# Payload_exterior_v1_0.net
KiCad netlist of a schematic drawn in EAGLE
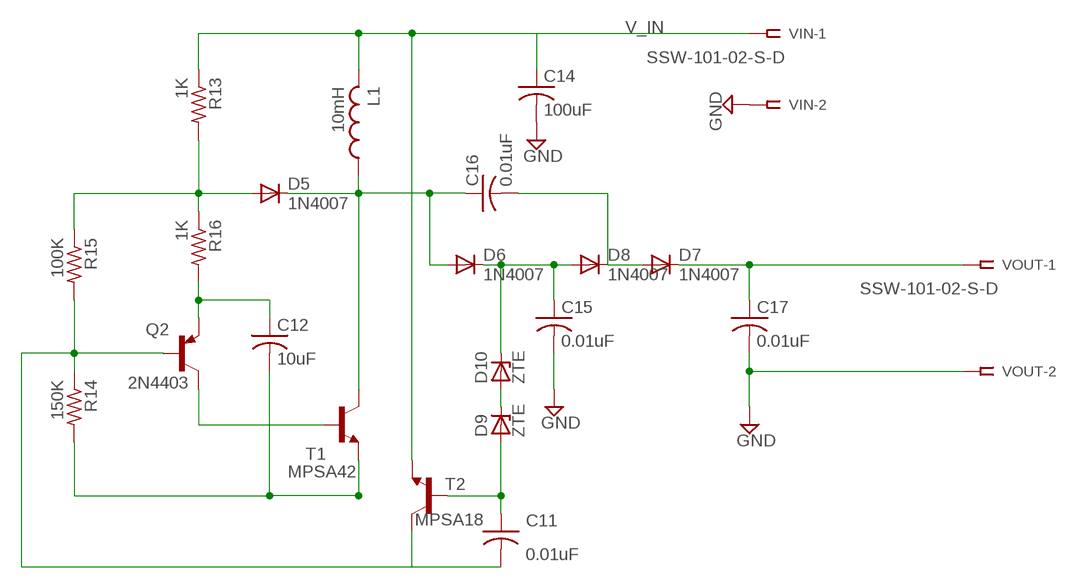
[diagram p0: schematic, sheet 1]

(export (version "E")
  (design (tool "Eeschema 10.0.6"))
  (components
    (comp (ref "C11")
      (value "0.01uF")
      (footprint "eagle-import:C050-035X075")
      (libsource (lib "eagle-import") (part "C-US050-035X075"))
    )
    (comp (ref "C12")
      (value "10uF")
      (footprint "eagle-import:C050-035X075")
      (libsource (lib "eagle-import") (part "C-US050-035X075"))
    )
    (comp (ref "C14")
      (value "100uF")
      (footprint "eagle-import:C050-035X075")
      (libsource (lib "eagle-import") (part "C-US050-035X075"))
    )
    (comp (ref "C15")
      (value "0.01uF")
      (footprint "eagle-import:C050-035X075")
      (libsource (lib "eagle-import") (part "C-US050-035X075"))
    )
    (comp (ref "C16")
      (value "0.01uF")
      (footprint "eagle-import:C050-035X075")
      (libsource (lib "eagle-import") (part "C-US050-035X075"))
    )
    (comp (ref "C17")
      (value "0.01uF")
      (footprint "eagle-import:C050-035X075")
      (libsource (lib "eagle-import") (part "C-US050-035X075"))
    )
    (comp (ref "D5")
      (value "1N4007")
      (footprint "eagle-import:DO41-10")
      (libsource (lib "eagle-import") (part "1N4004"))
    )
    (comp (ref "D6")
      (value "1N4007")
      (footprint "eagle-import:DO41-10")
      (libsource (lib "eagle-import") (part "1N4004"))
    )
    (comp (ref "D7")
      (value "1N4007")
      (footprint "eagle-import:DO41-10")
      (libsource (lib "eagle-import") (part "1N4004"))
    )
    (comp (ref "D8")
      (value "1N4007")
      (footprint "eagle-import:DO41-10")
      (libsource (lib "eagle-import") (part "1N4004"))
    )
    (comp (ref "D9")
      (value "ZTE")
      (footprint "eagle-import:DO35Z10")
      (libsource (lib "eagle-import") (part "ZTE"))
    )
    (comp (ref "D10")
      (value "ZTE")
      (footprint "eagle-import:DO35Z10")
      (libsource (lib "eagle-import") (part "ZTE"))
    )
    (comp (ref "L1")
      (value "10mH")
      (footprint "eagle-import:0207_12")
      (libsource (lib "eagle-import") (part "L-US0207/12"))
    )
    (comp (ref "Q2")
      (value "2N4403")
      (footprint "eagle-import:TO92-CBE")
      (libsource (lib "eagle-import") (part "2N4126"))
    )
    (comp (ref "R13")
      (value "1K")
      (footprint "eagle-import:0207_12")
      (libsource (lib "eagle-import") (part "R-US_0207/12"))
    )
    (comp (ref "R14")
      (value "150K")
      (footprint "eagle-import:0207_12")
      (libsource (lib "eagle-import") (part "R-US_0207/12"))
    )
    (comp (ref "R15")
      (value "100K")
      (footprint "eagle-import:0207_12")
      (libsource (lib "eagle-import") (part "R-US_0207/12"))
    )
    (comp (ref "R16")
      (value "1K")
      (footprint "eagle-import:0207_12")
      (libsource (lib "eagle-import") (part "R-US_0207/12"))
    )
    (comp (ref "T1")
      (value "MPSA42")
      (footprint "eagle-import:TO92-ECB")
      (libsource (lib "eagle-import") (part "2SC458"))
    )
    (comp (ref "T2")
      (value "MPSA18")
      (footprint "eagle-import:TO92-ECB")
      (libsource (lib "eagle-import") (part "2SC458"))
    )
    (comp (ref "VIN")
      (value "SSW-101-02-S-D")
      (footprint "eagle-import:SSW-101-02-S-D")
      (libsource (lib "eagle-import") (part "SSW-101-02-S-D"))
    )
    (comp (ref "VOUT")
      (value "SSW-101-02-S-D")
      (footprint "eagle-import:SSW-101-02-S-D")
      (libsource (lib "eagle-import") (part "SSW-101-02-S-D"))
    )
  )
  (nets
    (net (code "1") (name "/V_IN") (class "Default")
      (node (ref "C14") (pin "1") (pinfunction "1_1") (pintype "passive"))
      (node (ref "L1") (pin "2") (pinfunction "2_2") (pintype "passive"))
      (node (ref "R13") (pin "1") (pinfunction "1_1") (pintype "passive"))
      (node (ref "T2") (pin "E") (pinfunction "E_E") (pintype "passive"))
      (node (ref "VIN") (pin "1") (pinfunction "1_1") (pintype "passive"))
    )
    (net (code "2") (name "GND") (class "Default")
      (node (ref "C14") (pin "2") (pinfunction "2_2") (pintype "passive"))
      (node (ref "C15") (pin "2") (pinfunction "2_2") (pintype "passive"))
      (node (ref "C17") (pin "2") (pinfunction "2_2") (pintype "passive"))
      (node (ref "VIN") (pin "2") (pinfunction "1_2") (pintype "passive"))
      (node (ref "VOUT") (pin "2") (pinfunction "1_2") (pintype "passive"))
    )
    (net (code "3") (name "Net-(C11-Pad1)") (class "Default")
      (node (ref "C11") (pin "1") (pinfunction "1_1") (pintype "passive"))
      (node (ref "D9") (pin "A") (pinfunction "A_A") (pintype "passive"))
      (node (ref "T2") (pin "B") (pinfunction "B_B") (pintype "passive"))
    )
    (net (code "4") (name "Net-(C11-Pad2)") (class "Default")
      (node (ref "C11") (pin "2") (pinfunction "2_2") (pintype "passive"))
      (node (ref "Q2") (pin "B") (pinfunction "B_B") (pintype "passive"))
      (node (ref "R14") (pin "1") (pinfunction "1_1") (pintype "passive"))
      (node (ref "R15") (pin "2") (pinfunction "2_2") (pintype "passive"))
      (node (ref "T2") (pin "C") (pinfunction "C_C") (pintype "passive"))
    )
    (net (code "5") (name "Net-(C12-Pad1)") (class "Default")
      (node (ref "C12") (pin "1") (pinfunction "1_1") (pintype "passive"))
      (node (ref "Q2") (pin "E") (pinfunction "E_E") (pintype "passive"))
      (node (ref "R16") (pin "2") (pinfunction "2_2") (pintype "passive"))
    )
    (net (code "6") (name "Net-(C12-Pad2)") (class "Default")
      (node (ref "C12") (pin "2") (pinfunction "2_2") (pintype "passive"))
      (node (ref "R14") (pin "2") (pinfunction "2_2") (pintype "passive"))
      (node (ref "T1") (pin "E") (pinfunction "E_E") (pintype "passive"))
    )
    (net (code "7") (name "Net-(C15-Pad1)") (class "Default")
      (node (ref "C15") (pin "1") (pinfunction "1_1") (pintype "passive"))
      (node (ref "D10") (pin "C") (pinfunction "C_C") (pintype "passive"))
      (node (ref "D6") (pin "C") (pinfunction "C_C") (pintype "passive"))
      (node (ref "D8") (pin "A") (pinfunction "A_A") (pintype "passive"))
    )
    (net (code "8") (name "Net-(C16-Pad1)") (class "Default")
      (node (ref "C16") (pin "1") (pinfunction "1_1") (pintype "passive"))
      (node (ref "D5") (pin "C") (pinfunction "C_C") (pintype "passive"))
      (node (ref "D6") (pin "A") (pinfunction "A_A") (pintype "passive"))
      (node (ref "L1") (pin "1") (pinfunction "1_1") (pintype "passive"))
      (node (ref "T1") (pin "C") (pinfunction "C_C") (pintype "passive"))
    )
    (net (code "9") (name "Net-(C16-Pad2)") (class "Default")
      (node (ref "C16") (pin "2") (pinfunction "2_2") (pintype "passive"))
      (node (ref "D7") (pin "A") (pinfunction "A_A") (pintype "passive"))
      (node (ref "D8") (pin "C") (pinfunction "C_C") (pintype "passive"))
    )
    (net (code "10") (name "Net-(C17-Pad1)") (class "Default")
      (node (ref "C17") (pin "1") (pinfunction "1_1") (pintype "passive"))
      (node (ref "D7") (pin "C") (pinfunction "C_C") (pintype "passive"))
      (node (ref "VOUT") (pin "1") (pinfunction "1_1") (pintype "passive"))
    )
    (net (code "11") (name "Net-(D5-PadA)") (class "Default")
      (node (ref "D5") (pin "A") (pinfunction "A_A") (pintype "passive"))
      (node (ref "R13") (pin "2") (pinfunction "2_2") (pintype "passive"))
      (node (ref "R15") (pin "1") (pinfunction "1_1") (pintype "passive"))
      (node (ref "R16") (pin "1") (pinfunction "1_1") (pintype "passive"))
    )
    (net (code "12") (name "Net-(D10-PadA)") (class "Default")
      (node (ref "D10") (pin "A") (pinfunction "A_A") (pintype "passive"))
      (node (ref "D9") (pin "C") (pinfunction "C_C") (pintype "passive"))
    )
    (net (code "13") (name "Net-(Q2-PadC)") (class "Default")
      (node (ref "Q2") (pin "C") (pinfunction "C_C") (pintype "passive"))
      (node (ref "T1") (pin "B") (pinfunction "B_B") (pintype "passive"))
    )
  )
)
